# UI_Schematic.net
KiCad netlist of a schematic drawn in Altium Designer
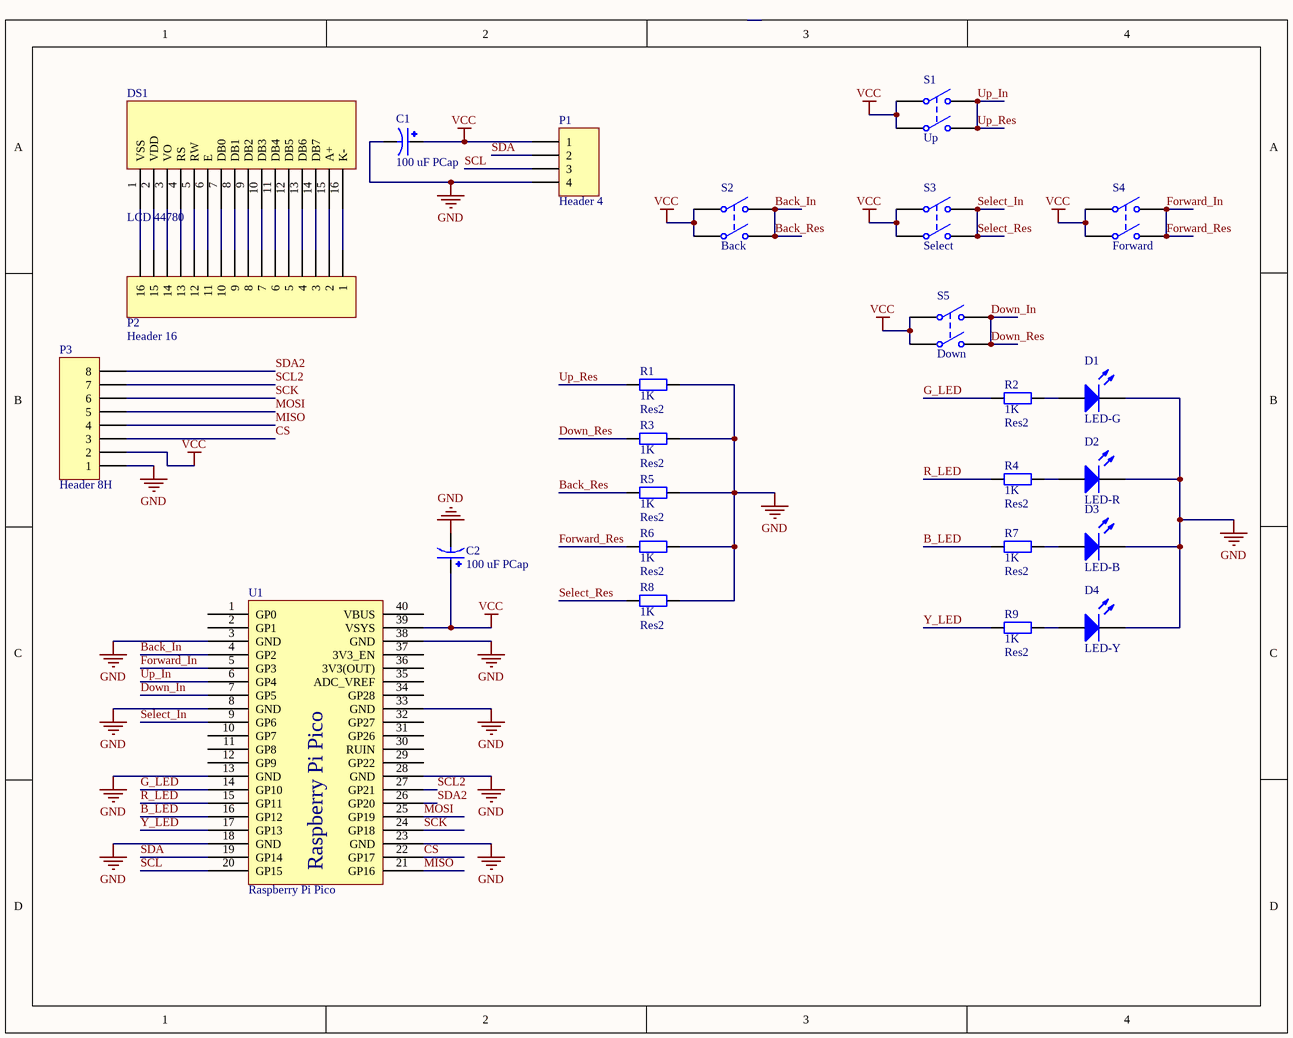
[diagram p0: UI Schematic.SchDoc]

(export (version "E")
  (design (tool "Eeschema 10.0.6"))
  (components
    (comp (ref "C1")
      (value "100 uF PCap")
      (footprint "Senior Design PCB Library:100uF PCap")
      (description "Capacitor; Aluminum Electrolytic; Radial Al Electrolytic Cap; 100uF 63V")
      (fields (field (name "MF") "Panasonic Electronic") (field (name "MP") "EEU-FC1J101"))
      (libsource (lib "") (part "100 uF PCap_1"))
    )
    (comp (ref "C2")
      (value "100 uF PCap")
      (footprint "Senior Design PCB Library:100uF PCap")
      (description "Capacitor; Aluminum Electrolytic; Radial Al Electrolytic Cap; 100uF 63V")
      (fields (field (name "MF") "Panasonic Electronic") (field (name "MP") "EEU-FC1J101"))
      (libsource (lib "Senior Design Schematic Library") (part "100 uF PCap"))
    )
    (comp (ref "D1")
      (value "LED-G")
      (footprint "LED-1")
      (description "Typical RED GaAs LED")
      (fields (field (name "PUBLISHER") "Altium Limited"))
      (libsource (lib "Miscellaneous Devices") (part "LED1"))
    )
    (comp (ref "D2")
      (value "LED-R")
      (footprint "LED-1")
      (description "Typical RED GaAs LED")
      (fields (field (name "PUBLISHER") "Altium Limited"))
      (libsource (lib "Miscellaneous Devices") (part "LED1"))
    )
    (comp (ref "D3")
      (value "LED-B")
      (footprint "LED-1")
      (description "Typical RED GaAs LED")
      (fields (field (name "PUBLISHER") "Altium Limited"))
      (libsource (lib "Miscellaneous Devices") (part "LED1"))
    )
    (comp (ref "D4")
      (value "LED-Y")
      (footprint "LED-1")
      (description "Typical RED GaAs LED")
      (fields (field (name "PUBLISHER") "Altium Limited"))
      (libsource (lib "Miscellaneous Devices") (part "LED1"))
    )
    (comp (ref "DS1")
      (value "LCD 44780")
      (footprint "OLED 16x2")
      (libsource (lib "ECE Lib 22") (part "LCD 44780"))
    )
    (comp (ref "P1")
      (value "Header 4")
      (footprint "HDR1X4")
      (description "Header, 4-Pin")
      (fields (field (name "PUBLISHER") "Altium Limited"))
      (libsource (lib "Miscellaneous Connectors") (part "Header 4"))
    )
    (comp (ref "P2")
      (value "Header 16")
      (footprint "HDR1X16")
      (description "Header, 16-Pin")
      (fields (field (name "PUBLISHER") "Altium Limited"))
      (libsource (lib "Miscellaneous Connectors") (part "Header 16"))
    )
    (comp (ref "P3")
      (value "Header 8H")
      (footprint "HDR1X8H")
      (description "Header, 8-Pin, Right Angle")
      (fields (field (name "PUBLISHER") "Altium Limited"))
      (libsource (lib "Miscellaneous Connectors") (part "Header 8H"))
    )
    (comp (ref "R1")
      (value "Res2")
      (footprint "AXIAL-0.4")
      (description "Resistor")
      (fields (field (name "ALTIUM_VALUE") "1K") (field (name "PUBLISHER") "Altium Limited"))
      (libsource (lib "Miscellaneous Devices") (part "Res2"))
    )
    (comp (ref "R2")
      (value "Res2")
      (footprint "AXIAL-0.4")
      (description "Resistor")
      (fields (field (name "ALTIUM_VALUE") "1K") (field (name "PUBLISHER") "Altium Limited"))
      (libsource (lib "Miscellaneous Devices") (part "Res2"))
    )
    (comp (ref "R3")
      (value "Res2")
      (footprint "AXIAL-0.4")
      (description "Resistor")
      (fields (field (name "ALTIUM_VALUE") "1K") (field (name "PUBLISHER") "Altium Limited"))
      (libsource (lib "Miscellaneous Devices") (part "Res2"))
    )
    (comp (ref "R4")
      (value "Res2")
      (footprint "AXIAL-0.4")
      (description "Resistor")
      (fields (field (name "ALTIUM_VALUE") "1K") (field (name "PUBLISHER") "Altium Limited"))
      (libsource (lib "Miscellaneous Devices") (part "Res2"))
    )
    (comp (ref "R5")
      (value "Res2")
      (footprint "AXIAL-0.4")
      (description "Resistor")
      (fields (field (name "ALTIUM_VALUE") "1K") (field (name "PUBLISHER") "Altium Limited"))
      (libsource (lib "Miscellaneous Devices") (part "Res2"))
    )
    (comp (ref "R6")
      (value "Res2")
      (footprint "AXIAL-0.4")
      (description "Resistor")
      (fields (field (name "ALTIUM_VALUE") "1K") (field (name "PUBLISHER") "Altium Limited"))
      (libsource (lib "Miscellaneous Devices") (part "Res2"))
    )
    (comp (ref "R7")
      (value "Res2")
      (footprint "AXIAL-0.4")
      (description "Resistor")
      (fields (field (name "ALTIUM_VALUE") "1K") (field (name "PUBLISHER") "Altium Limited"))
      (libsource (lib "Miscellaneous Devices") (part "Res2"))
    )
    (comp (ref "R8")
      (value "Res2")
      (footprint "AXIAL-0.4")
      (description "Resistor")
      (fields (field (name "ALTIUM_VALUE") "1K") (field (name "PUBLISHER") "Altium Limited"))
      (libsource (lib "Miscellaneous Devices") (part "Res2"))
    )
    (comp (ref "R9")
      (value "Res2")
      (footprint "AXIAL-0.4")
      (description "Resistor")
      (fields (field (name "ALTIUM_VALUE") "1K") (field (name "PUBLISHER") "Altium Limited"))
      (libsource (lib "Miscellaneous Devices") (part "Res2"))
    )
    (comp (ref "S1")
      (value "Up")
      (footprint "DPST-4")
      (description "Double-Pole, Single-Throw Switch")
      (fields (field (name "PUBLISHER") "Altium Limited"))
      (libsource (lib "Miscellaneous Devices") (part "SW-DPST"))
    )
    (comp (ref "S2")
      (value "Back")
      (footprint "DPST-4")
      (description "Double-Pole, Single-Throw Switch")
      (fields (field (name "PUBLISHER") "Altium Limited"))
      (libsource (lib "Miscellaneous Devices") (part "SW-DPST"))
    )
    (comp (ref "S3")
      (value "Select")
      (footprint "DPST-4")
      (description "Double-Pole, Single-Throw Switch")
      (fields (field (name "PUBLISHER") "Altium Limited"))
      (libsource (lib "Miscellaneous Devices") (part "SW-DPST"))
    )
    (comp (ref "S4")
      (value "Forward")
      (footprint "DPST-4")
      (description "Double-Pole, Single-Throw Switch")
      (fields (field (name "PUBLISHER") "Altium Limited"))
      (libsource (lib "Miscellaneous Devices") (part "SW-DPST"))
    )
    (comp (ref "S5")
      (value "Down")
      (footprint "DPST-4")
      (description "Double-Pole, Single-Throw Switch")
      (fields (field (name "PUBLISHER") "Altium Limited"))
      (libsource (lib "Miscellaneous Devices") (part "SW-DPST"))
    )
    (comp (ref "U1")
      (value "Raspberry Pi Pico")
      (footprint "Raspberry Pi Pico")
      (libsource (lib "ECE Lib 22") (part "Raspberry Pi Pico"))
    )
  )
  (nets
    (net (code "1") (name "/B_LED") (class "Default")
      (node (ref "R7") (pin "1") (pinfunction "1_1") (pintype "passive"))
      (node (ref "U1") (pin "16") (pinfunction "GP12_16") (pintype "passive"))
    )
    (net (code "2") (name "/Back_In") (class "Default")
      (node (ref "R5") (pin "1") (pinfunction "1_1") (pintype "passive"))
      (node (ref "S2") (pin "2") (pinfunction "NO1_2") (pintype "passive"))
      (node (ref "S2") (pin "4") (pinfunction "NO2_4") (pintype "passive"))
      (node (ref "U1") (pin "4") (pinfunction "GP2_4") (pintype "passive"))
    )
    (net (code "3") (name "/CS") (class "Default")
      (node (ref "P3") (pin "3") (pinfunction "3_3") (pintype "passive"))
      (node (ref "U1") (pin "22") (pinfunction "GP17_22") (pintype "passive"))
    )
    (net (code "4") (name "/Down_In") (class "Default")
      (node (ref "R3") (pin "1") (pinfunction "1_1") (pintype "passive"))
      (node (ref "S5") (pin "2") (pinfunction "NO1_2") (pintype "passive"))
      (node (ref "S5") (pin "4") (pinfunction "NO2_4") (pintype "passive"))
      (node (ref "U1") (pin "7") (pinfunction "GP5_7") (pintype "passive"))
    )
    (net (code "5") (name "/Forward_In") (class "Default")
      (node (ref "R6") (pin "1") (pinfunction "1_1") (pintype "passive"))
      (node (ref "S4") (pin "2") (pinfunction "NO1_2") (pintype "passive"))
      (node (ref "S4") (pin "4") (pinfunction "NO2_4") (pintype "passive"))
      (node (ref "U1") (pin "5") (pinfunction "GP3_5") (pintype "passive"))
    )
    (net (code "6") (name "/G_LED") (class "Default")
      (node (ref "R2") (pin "1") (pinfunction "1_1") (pintype "passive"))
      (node (ref "U1") (pin "14") (pinfunction "GP10_14") (pintype "passive"))
    )
    (net (code "7") (name "/MISO") (class "Default")
      (node (ref "P3") (pin "4") (pinfunction "4_4") (pintype "passive"))
      (node (ref "U1") (pin "21") (pinfunction "GP16_21") (pintype "passive"))
    )
    (net (code "8") (name "/MOSI") (class "Default")
      (node (ref "P3") (pin "5") (pinfunction "5_5") (pintype "passive"))
      (node (ref "U1") (pin "25") (pinfunction "GP19_25") (pintype "passive"))
    )
    (net (code "9") (name "/R_LED") (class "Default")
      (node (ref "R4") (pin "1") (pinfunction "1_1") (pintype "passive"))
      (node (ref "U1") (pin "15") (pinfunction "GP11_15") (pintype "passive"))
    )
    (net (code "10") (name "/SCK") (class "Default")
      (node (ref "P3") (pin "6") (pinfunction "6_6") (pintype "passive"))
      (node (ref "U1") (pin "24") (pinfunction "GP18_24") (pintype "passive"))
    )
    (net (code "11") (name "/SCL") (class "Default")
      (node (ref "P1") (pin "3") (pinfunction "3_3") (pintype "passive"))
      (node (ref "U1") (pin "20") (pinfunction "GP15_20") (pintype "passive"))
    )
    (net (code "12") (name "/SCL2") (class "Default")
      (node (ref "P3") (pin "7") (pinfunction "7_7") (pintype "passive"))
      (node (ref "U1") (pin "27") (pinfunction "GP21_27") (pintype "passive"))
    )
    (net (code "13") (name "/SDA") (class "Default")
      (node (ref "P1") (pin "2") (pinfunction "2_2") (pintype "passive"))
      (node (ref "U1") (pin "19") (pinfunction "GP14_19") (pintype "passive"))
    )
    (net (code "14") (name "/SDA2") (class "Default")
      (node (ref "P3") (pin "8") (pinfunction "8_8") (pintype "passive"))
      (node (ref "U1") (pin "26") (pinfunction "GP20_26") (pintype "passive"))
    )
    (net (code "15") (name "/Select_In") (class "Default")
      (node (ref "R8") (pin "1") (pinfunction "1_1") (pintype "passive"))
      (node (ref "S3") (pin "2") (pinfunction "NO1_2") (pintype "passive"))
      (node (ref "S3") (pin "4") (pinfunction "NO2_4") (pintype "passive"))
      (node (ref "U1") (pin "9") (pinfunction "GP6_9") (pintype "passive"))
    )
    (net (code "16") (name "/Up_In") (class "Default")
      (node (ref "R1") (pin "1") (pinfunction "1_1") (pintype "passive"))
      (node (ref "S1") (pin "2") (pinfunction "NO1_2") (pintype "passive"))
      (node (ref "S1") (pin "4") (pinfunction "NO2_4") (pintype "passive"))
      (node (ref "U1") (pin "6") (pinfunction "GP4_6") (pintype "passive"))
    )
    (net (code "17") (name "/Y_LED") (class "Default")
      (node (ref "R9") (pin "1") (pinfunction "1_1") (pintype "passive"))
      (node (ref "U1") (pin "17") (pinfunction "GP13_17") (pintype "passive"))
    )
    (net (code "18") (name "GND") (class "Default")
      (node (ref "C1") (pin "N") (pinfunction "N_N") (pintype "passive"))
      (node (ref "C2") (pin "N") (pinfunction "N_N") (pintype "passive"))
      (node (ref "D1") (pin "2") (pinfunction "K_2") (pintype "passive"))
      (node (ref "D2") (pin "2") (pinfunction "K_2") (pintype "passive"))
      (node (ref "D3") (pin "2") (pinfunction "K_2") (pintype "passive"))
      (node (ref "D4") (pin "2") (pinfunction "K_2") (pintype "passive"))
      (node (ref "P1") (pin "4") (pinfunction "4_4") (pintype "passive"))
      (node (ref "P3") (pin "1") (pinfunction "1_1") (pintype "passive"))
      (node (ref "R1") (pin "2") (pinfunction "2_2") (pintype "passive"))
      (node (ref "R3") (pin "2") (pinfunction "2_2") (pintype "passive"))
      (node (ref "R5") (pin "2") (pinfunction "2_2") (pintype "passive"))
      (node (ref "R6") (pin "2") (pinfunction "2_2") (pintype "passive"))
      (node (ref "R8") (pin "2") (pinfunction "2_2") (pintype "passive"))
      (node (ref "U1") (pin "13") (pinfunction "GND_13") (pintype "passive"))
      (node (ref "U1") (pin "18") (pinfunction "GND_18") (pintype "passive"))
      (node (ref "U1") (pin "23") (pinfunction "GND_23") (pintype "passive"))
      (node (ref "U1") (pin "28") (pinfunction "GND_28") (pintype "passive"))
      (node (ref "U1") (pin "3") (pinfunction "GND_3") (pintype "passive"))
      (node (ref "U1") (pin "33") (pinfunction "GND_33") (pintype "passive"))
      (node (ref "U1") (pin "38") (pinfunction "GND_38") (pintype "passive"))
      (node (ref "U1") (pin "8") (pinfunction "GND_8") (pintype "passive"))
    )
    (net (code "19") (name "Net-(D1-A)") (class "Default")
      (node (ref "D1") (pin "1") (pinfunction "A_1") (pintype "passive"))
      (node (ref "R2") (pin "2") (pinfunction "2_2") (pintype "passive"))
    )
    (net (code "20") (name "Net-(D2-A)") (class "Default")
      (node (ref "D2") (pin "1") (pinfunction "A_1") (pintype "passive"))
      (node (ref "R4") (pin "2") (pinfunction "2_2") (pintype "passive"))
    )
    (net (code "21") (name "Net-(D3-A)") (class "Default")
      (node (ref "D3") (pin "1") (pinfunction "A_1") (pintype "passive"))
      (node (ref "R7") (pin "2") (pinfunction "2_2") (pintype "passive"))
    )
    (net (code "22") (name "Net-(D4-A)") (class "Default")
      (node (ref "D4") (pin "1") (pinfunction "A_1") (pintype "passive"))
      (node (ref "R9") (pin "2") (pinfunction "2_2") (pintype "passive"))
    )
    (net (code "23") (name "Net-(DS1-A+)") (class "Default")
      (node (ref "DS1") (pin "15") (pinfunction "A+_15") (pintype "passive"))
      (node (ref "P2") (pin "2") (pinfunction "2_2") (pintype "passive"))
    )
    (net (code "24") (name "Net-(DS1-DB0)") (class "Default")
      (node (ref "DS1") (pin "7") (pinfunction "DB0_7") (pintype "passive"))
      (node (ref "P2") (pin "10") (pinfunction "10_10") (pintype "passive"))
    )
    (net (code "25") (name "Net-(DS1-DB1)") (class "Default")
      (node (ref "DS1") (pin "8") (pinfunction "DB1_8") (pintype "passive"))
      (node (ref "P2") (pin "9") (pinfunction "9_9") (pintype "passive"))
    )
    (net (code "26") (name "Net-(DS1-DB2)") (class "Default")
      (node (ref "DS1") (pin "9") (pinfunction "DB2_9") (pintype "passive"))
      (node (ref "P2") (pin "8") (pinfunction "8_8") (pintype "passive"))
    )
    (net (code "27") (name "Net-(DS1-DB3)") (class "Default")
      (node (ref "DS1") (pin "10") (pinfunction "DB3_10") (pintype "passive"))
      (node (ref "P2") (pin "7") (pinfunction "7_7") (pintype "passive"))
    )
    (net (code "28") (name "Net-(DS1-DB4)") (class "Default")
      (node (ref "DS1") (pin "11") (pinfunction "DB4_11") (pintype "passive"))
      (node (ref "P2") (pin "6") (pinfunction "6_6") (pintype "passive"))
    )
    (net (code "29") (name "Net-(DS1-DB5)") (class "Default")
      (node (ref "DS1") (pin "12") (pinfunction "DB5_12") (pintype "passive"))
      (node (ref "P2") (pin "5") (pinfunction "5_5") (pintype "passive"))
    )
    (net (code "30") (name "Net-(DS1-DB6)") (class "Default")
      (node (ref "DS1") (pin "13") (pinfunction "DB6_13") (pintype "passive"))
      (node (ref "P2") (pin "4") (pinfunction "4_4") (pintype "passive"))
    )
    (net (code "31") (name "Net-(DS1-DB7)") (class "Default")
      (node (ref "DS1") (pin "14") (pinfunction "DB7_14") (pintype "passive"))
      (node (ref "P2") (pin "3") (pinfunction "3_3") (pintype "passive"))
    )
    (net (code "32") (name "Net-(DS1-E)") (class "Default")
      (node (ref "DS1") (pin "6") (pinfunction "E_6") (pintype "passive"))
      (node (ref "P2") (pin "11") (pinfunction "11_11") (pintype "passive"))
    )
    (net (code "33") (name "Net-(DS1-K-)") (class "Default")
      (node (ref "DS1") (pin "16") (pinfunction "K-_16") (pintype "passive"))
      (node (ref "P2") (pin "1") (pinfunction "1_1") (pintype "passive"))
    )
    (net (code "34") (name "Net-(DS1-RS)") (class "Default")
      (node (ref "DS1") (pin "4") (pinfunction "RS_4") (pintype "passive"))
      (node (ref "P2") (pin "13") (pinfunction "13_13") (pintype "passive"))
    )
    (net (code "35") (name "Net-(DS1-RW)") (class "Default")
      (node (ref "DS1") (pin "5") (pinfunction "RW_5") (pintype "passive"))
      (node (ref "P2") (pin "12") (pinfunction "12_12") (pintype "passive"))
    )
    (net (code "36") (name "Net-(DS1-VDD)") (class "Default")
      (node (ref "DS1") (pin "2") (pinfunction "VDD_2") (pintype "passive"))
      (node (ref "P2") (pin "15") (pinfunction "15_15") (pintype "passive"))
    )
    (net (code "37") (name "Net-(DS1-VO)") (class "Default")
      (node (ref "DS1") (pin "3") (pinfunction "VO_3") (pintype "passive"))
      (node (ref "P2") (pin "14") (pinfunction "14_14") (pintype "passive"))
    )
    (net (code "38") (name "Net-(DS1-VSS)") (class "Default")
      (node (ref "DS1") (pin "1") (pinfunction "VSS_1") (pintype "passive"))
      (node (ref "P2") (pin "16") (pinfunction "16_16") (pintype "passive"))
    )
    (net (code "39") (name "VCC") (class "Default")
      (node (ref "C1") (pin "P") (pinfunction "P_P") (pintype "passive"))
      (node (ref "C2") (pin "P") (pinfunction "P_P") (pintype "passive"))
      (node (ref "P1") (pin "1") (pinfunction "1_1") (pintype "passive"))
      (node (ref "P3") (pin "2") (pinfunction "2_2") (pintype "passive"))
      (node (ref "S1") (pin "1") (pinfunction "COMMON1_1") (pintype "passive"))
      (node (ref "S1") (pin "3") (pinfunction "COMMON2_3") (pintype "passive"))
      (node (ref "S2") (pin "1") (pinfunction "COMMON1_1") (pintype "passive"))
      (node (ref "S2") (pin "3") (pinfunction "COMMON2_3") (pintype "passive"))
      (node (ref "S3") (pin "1") (pinfunction "COMMON1_1") (pintype "passive"))
      (node (ref "S3") (pin "3") (pinfunction "COMMON2_3") (pintype "passive"))
      (node (ref "S4") (pin "1") (pinfunction "COMMON1_1") (pintype "passive"))
      (node (ref "S4") (pin "3") (pinfunction "COMMON2_3") (pintype "passive"))
      (node (ref "S5") (pin "1") (pinfunction "COMMON1_1") (pintype "passive"))
      (node (ref "S5") (pin "3") (pinfunction "COMMON2_3") (pintype "passive"))
      (node (ref "U1") (pin "39") (pinfunction "VSYS_39") (pintype "passive"))
    )
    (net (code "40") (name "unconnected-(U1-3V3(OUT)-Pad36)") (class "Default")
      (node (ref "U1") (pin "36") (pinfunction "3V3(OUT)_36") (pintype "passive"))
    )
    (net (code "41") (name "unconnected-(U1-3V3_EN-Pad37)") (class "Default")
      (node (ref "U1") (pin "37") (pinfunction "3V3_EN_37") (pintype "passive"))
    )
    (net (code "42") (name "unconnected-(U1-ADC_VREF-Pad35)") (class "Default")
      (node (ref "U1") (pin "35") (pinfunction "ADC_VREF_35") (pintype "passive"))
    )
    (net (code "43") (name "unconnected-(U1-GP0-Pad1)") (class "Default")
      (node (ref "U1") (pin "1") (pinfunction "GP0_1") (pintype "passive"))
    )
    (net (code "44") (name "unconnected-(U1-GP1-Pad2)") (class "Default")
      (node (ref "U1") (pin "2") (pinfunction "GP1_2") (pintype "passive"))
    )
    (net (code "45") (name "unconnected-(U1-GP7-Pad10)") (class "Default")
      (node (ref "U1") (pin "10") (pinfunction "GP7_10") (pintype "passive"))
    )
    (net (code "46") (name "unconnected-(U1-GP8-Pad11)") (class "Default")
      (node (ref "U1") (pin "11") (pinfunction "GP8_11") (pintype "passive"))
    )
    (net (code "47") (name "unconnected-(U1-GP9-Pad12)") (class "Default")
      (node (ref "U1") (pin "12") (pinfunction "GP9_12") (pintype "passive"))
    )
    (net (code "48") (name "unconnected-(U1-GP22-Pad29)") (class "Default")
      (node (ref "U1") (pin "29") (pinfunction "GP22_29") (pintype "passive"))
    )
    (net (code "49") (name "unconnected-(U1-GP26-Pad31)") (class "Default")
      (node (ref "U1") (pin "31") (pinfunction "GP26_31") (pintype "passive"))
    )
    (net (code "50") (name "unconnected-(U1-GP27-Pad32)") (class "Default")
      (node (ref "U1") (pin "32") (pinfunction "GP27_32") (pintype "passive"))
    )
    (net (code "51") (name "unconnected-(U1-GP28-Pad34)") (class "Default")
      (node (ref "U1") (pin "34") (pinfunction "GP28_34") (pintype "passive"))
    )
    (net (code "52") (name "unconnected-(U1-RUIN-Pad30)") (class "Default")
      (node (ref "U1") (pin "30") (pinfunction "RUIN_30") (pintype "passive"))
    )
    (net (code "53") (name "unconnected-(U1-VBUS-Pad40)") (class "Default")
      (node (ref "U1") (pin "40") (pinfunction "VBUS_40") (pintype "passive"))
    )
  )
)
